# cubey_v3_1.net
KiCad netlist of a schematic drawn in EAGLE
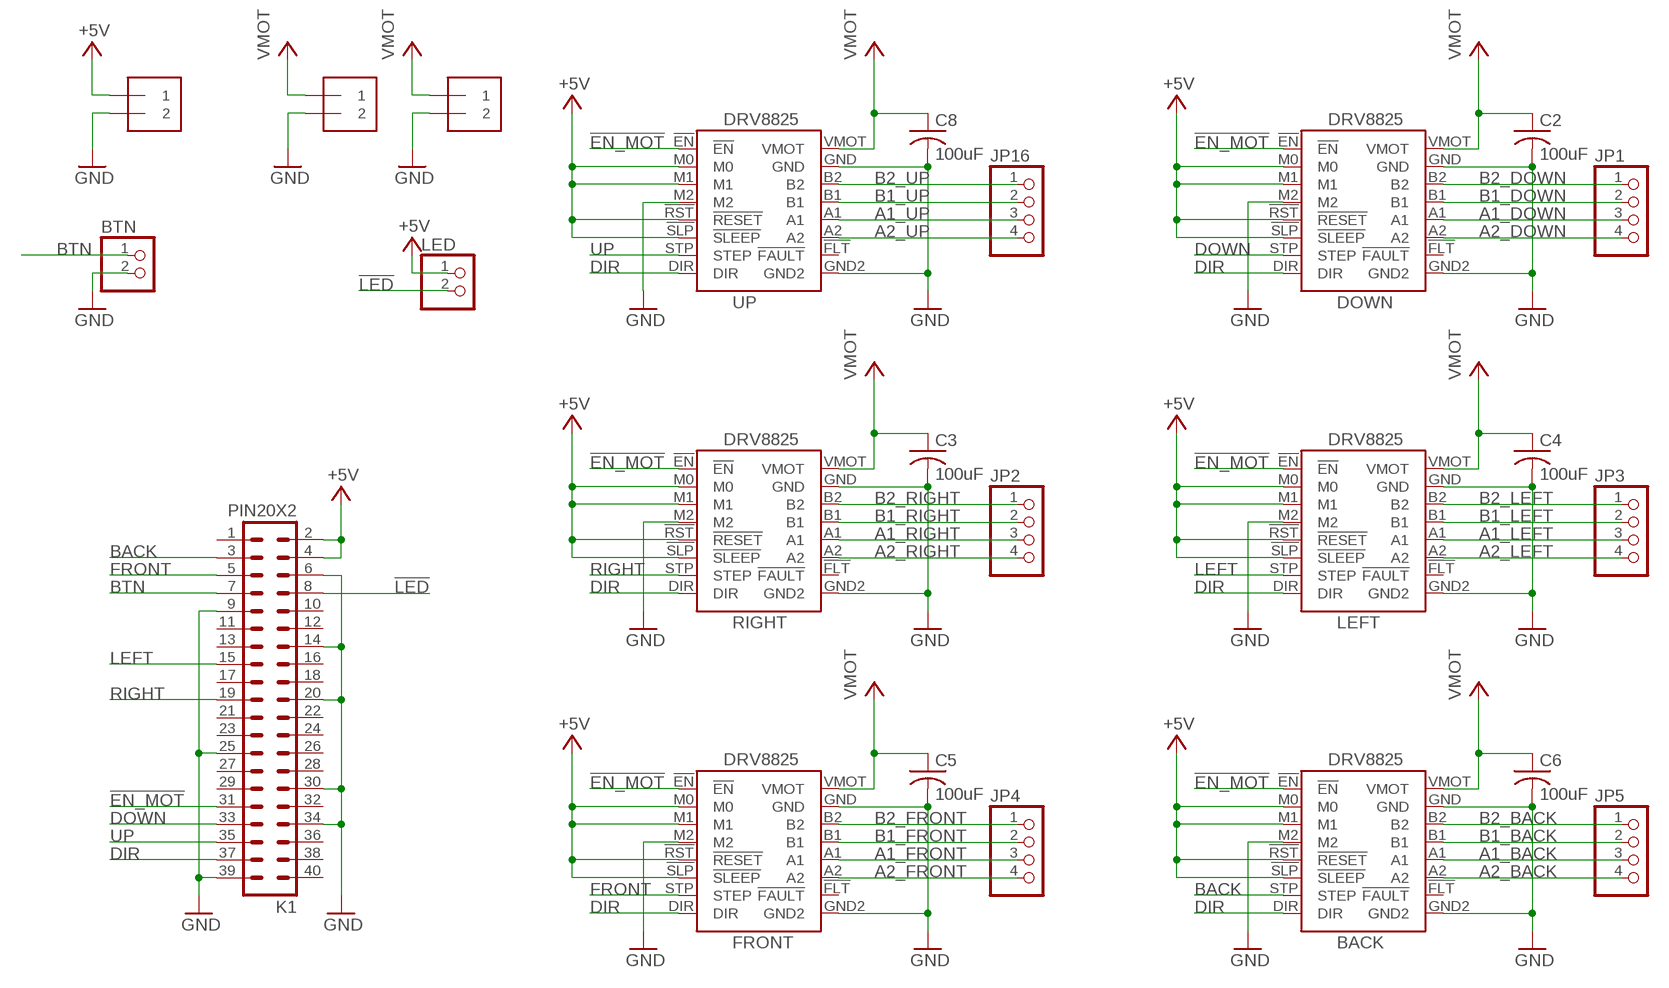
[diagram p0: schematic, sheet 1]

(export (version "E")
  (design (tool "Eeschema 10.0.6"))
  (components
    (comp (ref "5V_PWR")
      (value "1X2-3.5MM")
      (footprint "eagle-import:1X2-3.5MM")
      (libsource (lib "eagle-import") (part "1X2-3.5MM"))
    )
    (comp (ref "BACK")
      (value "DRV_8825_SOCKET")
      (footprint "eagle-import:DRV_8825_DIP")
      (libsource (lib "eagle-import") (part "DRV_8825_SOCKET"))
    )
    (comp (ref "BTN")
      (value "PINHD-1X2")
      (footprint "eagle-import:1X02")
      (libsource (lib "eagle-import") (part "PINHD-1X2"))
    )
    (comp (ref "C2")
      (value "100uF")
      (footprint "eagle-import:C025-025X050")
      (libsource (lib "eagle-import") (part "C-US025-025X050"))
    )
    (comp (ref "C3")
      (value "100uF")
      (footprint "eagle-import:C025-025X050")
      (libsource (lib "eagle-import") (part "C-US025-025X050"))
    )
    (comp (ref "C4")
      (value "100uF")
      (footprint "eagle-import:C025-025X050")
      (libsource (lib "eagle-import") (part "C-US025-025X050"))
    )
    (comp (ref "C5")
      (value "100uF")
      (footprint "eagle-import:C025-025X050")
      (libsource (lib "eagle-import") (part "C-US025-025X050"))
    )
    (comp (ref "C6")
      (value "100uF")
      (footprint "eagle-import:C025-025X050")
      (libsource (lib "eagle-import") (part "C-US025-025X050"))
    )
    (comp (ref "C8")
      (value "100uF")
      (footprint "eagle-import:C025-025X050")
      (libsource (lib "eagle-import") (part "C-US025-025X050"))
    )
    (comp (ref "DOWN")
      (value "DRV_8825_SOCKET")
      (footprint "eagle-import:DRV_8825_DIP")
      (libsource (lib "eagle-import") (part "DRV_8825_SOCKET"))
    )
    (comp (ref "FRONT")
      (value "DRV_8825_SOCKET")
      (footprint "eagle-import:DRV_8825_DIP")
      (libsource (lib "eagle-import") (part "DRV_8825_SOCKET"))
    )
    (comp (ref "JP1")
      (value "PINHD-1X4")
      (footprint "eagle-import:1X04")
      (libsource (lib "eagle-import") (part "PINHD-1X4"))
    )
    (comp (ref "JP2")
      (value "PINHD-1X4")
      (footprint "eagle-import:1X04")
      (libsource (lib "eagle-import") (part "PINHD-1X4"))
    )
    (comp (ref "JP3")
      (value "PINHD-1X4")
      (footprint "eagle-import:1X04")
      (libsource (lib "eagle-import") (part "PINHD-1X4"))
    )
    (comp (ref "JP4")
      (value "PINHD-1X4")
      (footprint "eagle-import:1X04")
      (libsource (lib "eagle-import") (part "PINHD-1X4"))
    )
    (comp (ref "JP5")
      (value "PINHD-1X4")
      (footprint "eagle-import:1X04")
      (libsource (lib "eagle-import") (part "PINHD-1X4"))
    )
    (comp (ref "JP16")
      (value "PINHD-1X4")
      (footprint "eagle-import:1X04")
      (libsource (lib "eagle-import") (part "PINHD-1X4"))
    )
    (comp (ref "K1")
      (value "PIN20X2")
      (footprint "eagle-import:PIN_20X2")
      (libsource (lib "eagle-import") (part "PIN20X2"))
    )
    (comp (ref "LED")
      (value "PINHD-1X2")
      (footprint "eagle-import:1X02")
      (libsource (lib "eagle-import") (part "PINHD-1X2"))
    )
    (comp (ref "LEFT")
      (value "DRV_8825_SOCKET")
      (footprint "eagle-import:DRV_8825_DIP")
      (libsource (lib "eagle-import") (part "DRV_8825_SOCKET"))
    )
    (comp (ref "MOT_PWR")
      (value "1X2-3.5MM")
      (footprint "eagle-import:1X2-3.5MM")
      (libsource (lib "eagle-import") (part "1X2-3.5MM"))
    )
    (comp (ref "MOT_PWR1")
      (value "1X2-3.5MM")
      (footprint "eagle-import:1X2-3.5MM")
      (libsource (lib "eagle-import") (part "1X2-3.5MM"))
    )
    (comp (ref "RIGHT")
      (value "DRV_8825_SOCKET")
      (footprint "eagle-import:DRV_8825_DIP")
      (libsource (lib "eagle-import") (part "DRV_8825_SOCKET"))
    )
    (comp (ref "UP")
      (value "DRV_8825_SOCKET")
      (footprint "eagle-import:DRV_8825_DIP")
      (libsource (lib "eagle-import") (part "DRV_8825_SOCKET"))
    )
  )
  (nets
    (net (code "1") (name "+5V") (class "Default")
      (node (ref "5V_PWR") (pin "1") (pinfunction "1_1") (pintype "passive"))
      (node (ref "BACK") (pin "!RST") (pinfunction "~{RESET}_!RST") (pintype "bidirectional"))
      (node (ref "BACK") (pin "!SLP") (pinfunction "~{SLEEP}_!SLP") (pintype "bidirectional"))
      (node (ref "BACK") (pin "M0") (pinfunction "M0_M0") (pintype "bidirectional"))
      (node (ref "BACK") (pin "M1") (pinfunction "M1_M1") (pintype "bidirectional"))
      (node (ref "DOWN") (pin "!RST") (pinfunction "~{RESET}_!RST") (pintype "bidirectional"))
      (node (ref "DOWN") (pin "!SLP") (pinfunction "~{SLEEP}_!SLP") (pintype "bidirectional"))
      (node (ref "DOWN") (pin "M0") (pinfunction "M0_M0") (pintype "bidirectional"))
      (node (ref "DOWN") (pin "M1") (pinfunction "M1_M1") (pintype "bidirectional"))
      (node (ref "FRONT") (pin "!RST") (pinfunction "~{RESET}_!RST") (pintype "bidirectional"))
      (node (ref "FRONT") (pin "!SLP") (pinfunction "~{SLEEP}_!SLP") (pintype "bidirectional"))
      (node (ref "FRONT") (pin "M0") (pinfunction "M0_M0") (pintype "bidirectional"))
      (node (ref "FRONT") (pin "M1") (pinfunction "M1_M1") (pintype "bidirectional"))
      (node (ref "K1") (pin "2") (pinfunction "2_2") (pintype "passive"))
      (node (ref "K1") (pin "4") (pinfunction "4_4") (pintype "passive"))
      (node (ref "LED") (pin "1") (pinfunction "1_1") (pintype "passive"))
      (node (ref "LEFT") (pin "!RST") (pinfunction "~{RESET}_!RST") (pintype "bidirectional"))
      (node (ref "LEFT") (pin "!SLP") (pinfunction "~{SLEEP}_!SLP") (pintype "bidirectional"))
      (node (ref "LEFT") (pin "M0") (pinfunction "M0_M0") (pintype "bidirectional"))
      (node (ref "LEFT") (pin "M1") (pinfunction "M1_M1") (pintype "bidirectional"))
      (node (ref "RIGHT") (pin "!RST") (pinfunction "~{RESET}_!RST") (pintype "bidirectional"))
      (node (ref "RIGHT") (pin "!SLP") (pinfunction "~{SLEEP}_!SLP") (pintype "bidirectional"))
      (node (ref "RIGHT") (pin "M0") (pinfunction "M0_M0") (pintype "bidirectional"))
      (node (ref "RIGHT") (pin "M1") (pinfunction "M1_M1") (pintype "bidirectional"))
      (node (ref "UP") (pin "!RST") (pinfunction "~{RESET}_!RST") (pintype "bidirectional"))
      (node (ref "UP") (pin "!SLP") (pinfunction "~{SLEEP}_!SLP") (pintype "bidirectional"))
      (node (ref "UP") (pin "M0") (pinfunction "M0_M0") (pintype "bidirectional"))
      (node (ref "UP") (pin "M1") (pinfunction "M1_M1") (pintype "bidirectional"))
    )
    (net (code "2") (name "/A1_BACK") (class "Default")
      (node (ref "BACK") (pin "A1") (pinfunction "A1_A1") (pintype "power_in"))
      (node (ref "JP5") (pin "3") (pinfunction "3_3") (pintype "passive"))
    )
    (net (code "3") (name "/A1_DOWN") (class "Default")
      (node (ref "DOWN") (pin "A1") (pinfunction "A1_A1") (pintype "power_in"))
      (node (ref "JP1") (pin "3") (pinfunction "3_3") (pintype "passive"))
    )
    (net (code "4") (name "/A1_FRONT") (class "Default")
      (node (ref "FRONT") (pin "A1") (pinfunction "A1_A1") (pintype "power_in"))
      (node (ref "JP4") (pin "3") (pinfunction "3_3") (pintype "passive"))
    )
    (net (code "5") (name "/A1_LEFT") (class "Default")
      (node (ref "JP3") (pin "3") (pinfunction "3_3") (pintype "passive"))
      (node (ref "LEFT") (pin "A1") (pinfunction "A1_A1") (pintype "power_in"))
    )
    (net (code "6") (name "/A1_RIGHT") (class "Default")
      (node (ref "JP2") (pin "3") (pinfunction "3_3") (pintype "passive"))
      (node (ref "RIGHT") (pin "A1") (pinfunction "A1_A1") (pintype "power_in"))
    )
    (net (code "7") (name "/A1_UP") (class "Default")
      (node (ref "JP16") (pin "3") (pinfunction "3_3") (pintype "passive"))
      (node (ref "UP") (pin "A1") (pinfunction "A1_A1") (pintype "power_in"))
    )
    (net (code "8") (name "/A2_BACK") (class "Default")
      (node (ref "BACK") (pin "A2") (pinfunction "A2_A2") (pintype "power_in"))
      (node (ref "JP5") (pin "4") (pinfunction "4_4") (pintype "passive"))
    )
    (net (code "9") (name "/A2_DOWN") (class "Default")
      (node (ref "DOWN") (pin "A2") (pinfunction "A2_A2") (pintype "power_in"))
      (node (ref "JP1") (pin "4") (pinfunction "4_4") (pintype "passive"))
    )
    (net (code "10") (name "/A2_FRONT") (class "Default")
      (node (ref "FRONT") (pin "A2") (pinfunction "A2_A2") (pintype "power_in"))
      (node (ref "JP4") (pin "4") (pinfunction "4_4") (pintype "passive"))
    )
    (net (code "11") (name "/A2_LEFT") (class "Default")
      (node (ref "JP3") (pin "4") (pinfunction "4_4") (pintype "passive"))
      (node (ref "LEFT") (pin "A2") (pinfunction "A2_A2") (pintype "power_in"))
    )
    (net (code "12") (name "/A2_RIGHT") (class "Default")
      (node (ref "JP2") (pin "4") (pinfunction "4_4") (pintype "passive"))
      (node (ref "RIGHT") (pin "A2") (pinfunction "A2_A2") (pintype "power_in"))
    )
    (net (code "13") (name "/A2_UP") (class "Default")
      (node (ref "JP16") (pin "4") (pinfunction "4_4") (pintype "passive"))
      (node (ref "UP") (pin "A2") (pinfunction "A2_A2") (pintype "power_in"))
    )
    (net (code "14") (name "/B1_BACK") (class "Default")
      (node (ref "BACK") (pin "B1") (pinfunction "B1_B1") (pintype "power_in"))
      (node (ref "JP5") (pin "2") (pinfunction "2_2") (pintype "passive"))
    )
    (net (code "15") (name "/B1_DOWN") (class "Default")
      (node (ref "DOWN") (pin "B1") (pinfunction "B1_B1") (pintype "power_in"))
      (node (ref "JP1") (pin "2") (pinfunction "2_2") (pintype "passive"))
    )
    (net (code "16") (name "/B1_FRONT") (class "Default")
      (node (ref "FRONT") (pin "B1") (pinfunction "B1_B1") (pintype "power_in"))
      (node (ref "JP4") (pin "2") (pinfunction "2_2") (pintype "passive"))
    )
    (net (code "17") (name "/B1_LEFT") (class "Default")
      (node (ref "JP3") (pin "2") (pinfunction "2_2") (pintype "passive"))
      (node (ref "LEFT") (pin "B1") (pinfunction "B1_B1") (pintype "power_in"))
    )
    (net (code "18") (name "/B1_RIGHT") (class "Default")
      (node (ref "JP2") (pin "2") (pinfunction "2_2") (pintype "passive"))
      (node (ref "RIGHT") (pin "B1") (pinfunction "B1_B1") (pintype "power_in"))
    )
    (net (code "19") (name "/B1_UP") (class "Default")
      (node (ref "JP16") (pin "2") (pinfunction "2_2") (pintype "passive"))
      (node (ref "UP") (pin "B1") (pinfunction "B1_B1") (pintype "power_in"))
    )
    (net (code "20") (name "/B2_BACK") (class "Default")
      (node (ref "BACK") (pin "B2") (pinfunction "B2_B2") (pintype "power_in"))
      (node (ref "JP5") (pin "1") (pinfunction "1_1") (pintype "passive"))
    )
    (net (code "21") (name "/B2_DOWN") (class "Default")
      (node (ref "DOWN") (pin "B2") (pinfunction "B2_B2") (pintype "power_in"))
      (node (ref "JP1") (pin "1") (pinfunction "1_1") (pintype "passive"))
    )
    (net (code "22") (name "/B2_FRONT") (class "Default")
      (node (ref "FRONT") (pin "B2") (pinfunction "B2_B2") (pintype "power_in"))
      (node (ref "JP4") (pin "1") (pinfunction "1_1") (pintype "passive"))
    )
    (net (code "23") (name "/B2_LEFT") (class "Default")
      (node (ref "JP3") (pin "1") (pinfunction "1_1") (pintype "passive"))
      (node (ref "LEFT") (pin "B2") (pinfunction "B2_B2") (pintype "power_in"))
    )
    (net (code "24") (name "/B2_RIGHT") (class "Default")
      (node (ref "JP2") (pin "1") (pinfunction "1_1") (pintype "passive"))
      (node (ref "RIGHT") (pin "B2") (pinfunction "B2_B2") (pintype "power_in"))
    )
    (net (code "25") (name "/B2_UP") (class "Default")
      (node (ref "JP16") (pin "1") (pinfunction "1_1") (pintype "passive"))
      (node (ref "UP") (pin "B2") (pinfunction "B2_B2") (pintype "power_in"))
    )
    (net (code "26") (name "/BACK") (class "Default")
      (node (ref "BACK") (pin "STP") (pinfunction "STEP_STP") (pintype "bidirectional"))
      (node (ref "K1") (pin "3") (pinfunction "3_3") (pintype "passive"))
    )
    (net (code "27") (name "/BTN") (class "Default")
      (node (ref "BTN") (pin "1") (pinfunction "1_1") (pintype "passive"))
      (node (ref "K1") (pin "7") (pinfunction "7_7") (pintype "passive"))
    )
    (net (code "28") (name "/DIR") (class "Default")
      (node (ref "BACK") (pin "DIR") (pinfunction "DIR_DIR") (pintype "bidirectional"))
      (node (ref "DOWN") (pin "DIR") (pinfunction "DIR_DIR") (pintype "bidirectional"))
      (node (ref "FRONT") (pin "DIR") (pinfunction "DIR_DIR") (pintype "bidirectional"))
      (node (ref "K1") (pin "37") (pinfunction "37_37") (pintype "passive"))
      (node (ref "LEFT") (pin "DIR") (pinfunction "DIR_DIR") (pintype "bidirectional"))
      (node (ref "RIGHT") (pin "DIR") (pinfunction "DIR_DIR") (pintype "bidirectional"))
      (node (ref "UP") (pin "DIR") (pinfunction "DIR_DIR") (pintype "bidirectional"))
    )
    (net (code "29") (name "/DOWN") (class "Default")
      (node (ref "DOWN") (pin "STP") (pinfunction "STEP_STP") (pintype "bidirectional"))
      (node (ref "K1") (pin "33") (pinfunction "33_33") (pintype "passive"))
    )
    (net (code "30") (name "/FRONT") (class "Default")
      (node (ref "FRONT") (pin "STP") (pinfunction "STEP_STP") (pintype "bidirectional"))
      (node (ref "K1") (pin "5") (pinfunction "5_5") (pintype "passive"))
    )
    (net (code "31") (name "/LEFT") (class "Default")
      (node (ref "K1") (pin "15") (pinfunction "15_15") (pintype "passive"))
      (node (ref "LEFT") (pin "STP") (pinfunction "STEP_STP") (pintype "bidirectional"))
    )
    (net (code "32") (name "/RIGHT") (class "Default")
      (node (ref "K1") (pin "19") (pinfunction "19_19") (pintype "passive"))
      (node (ref "RIGHT") (pin "STP") (pinfunction "STEP_STP") (pintype "bidirectional"))
    )
    (net (code "33") (name "/UP") (class "Default")
      (node (ref "K1") (pin "35") (pinfunction "35_35") (pintype "passive"))
      (node (ref "UP") (pin "STP") (pinfunction "STEP_STP") (pintype "bidirectional"))
    )
    (net (code "34") (name "/~{EN_MOT}") (class "Default")
      (node (ref "BACK") (pin "!EN") (pinfunction "~{EN}_!EN") (pintype "bidirectional"))
      (node (ref "DOWN") (pin "!EN") (pinfunction "~{EN}_!EN") (pintype "bidirectional"))
      (node (ref "FRONT") (pin "!EN") (pinfunction "~{EN}_!EN") (pintype "bidirectional"))
      (node (ref "K1") (pin "31") (pinfunction "31_31") (pintype "passive"))
      (node (ref "LEFT") (pin "!EN") (pinfunction "~{EN}_!EN") (pintype "bidirectional"))
      (node (ref "RIGHT") (pin "!EN") (pinfunction "~{EN}_!EN") (pintype "bidirectional"))
      (node (ref "UP") (pin "!EN") (pinfunction "~{EN}_!EN") (pintype "bidirectional"))
    )
    (net (code "35") (name "/~{LED}") (class "Default")
      (node (ref "K1") (pin "8") (pinfunction "8_8") (pintype "passive"))
      (node (ref "LED") (pin "2") (pinfunction "2_2") (pintype "passive"))
    )
    (net (code "36") (name "GND") (class "Default")
      (node (ref "5V_PWR") (pin "2") (pinfunction "2_2") (pintype "passive"))
      (node (ref "BACK") (pin "GND") (pinfunction "GND_GND") (pintype "power_in"))
      (node (ref "BACK") (pin "GND2") (pinfunction "GND2_GND2") (pintype "power_in"))
      (node (ref "BACK") (pin "M2") (pinfunction "M2_M2") (pintype "bidirectional"))
      (node (ref "BTN") (pin "2") (pinfunction "2_2") (pintype "passive"))
      (node (ref "C2") (pin "2") (pinfunction "2_2") (pintype "passive"))
      (node (ref "C3") (pin "2") (pinfunction "2_2") (pintype "passive"))
      (node (ref "C4") (pin "2") (pinfunction "2_2") (pintype "passive"))
      (node (ref "C5") (pin "2") (pinfunction "2_2") (pintype "passive"))
      (node (ref "C6") (pin "2") (pinfunction "2_2") (pintype "passive"))
      (node (ref "C8") (pin "2") (pinfunction "2_2") (pintype "passive"))
      (node (ref "DOWN") (pin "GND") (pinfunction "GND_GND") (pintype "power_in"))
      (node (ref "DOWN") (pin "GND2") (pinfunction "GND2_GND2") (pintype "power_in"))
      (node (ref "DOWN") (pin "M2") (pinfunction "M2_M2") (pintype "bidirectional"))
      (node (ref "FRONT") (pin "GND") (pinfunction "GND_GND") (pintype "power_in"))
      (node (ref "FRONT") (pin "GND2") (pinfunction "GND2_GND2") (pintype "power_in"))
      (node (ref "FRONT") (pin "M2") (pinfunction "M2_M2") (pintype "bidirectional"))
      (node (ref "K1") (pin "14") (pinfunction "14_14") (pintype "passive"))
      (node (ref "K1") (pin "20") (pinfunction "20_20") (pintype "passive"))
      (node (ref "K1") (pin "25") (pinfunction "25_25") (pintype "passive"))
      (node (ref "K1") (pin "30") (pinfunction "30_30") (pintype "passive"))
      (node (ref "K1") (pin "34") (pinfunction "34_34") (pintype "passive"))
      (node (ref "K1") (pin "39") (pinfunction "39_39") (pintype "passive"))
      (node (ref "K1") (pin "6") (pinfunction "6_6") (pintype "passive"))
      (node (ref "K1") (pin "9") (pinfunction "9_9") (pintype "passive"))
      (node (ref "LEFT") (pin "GND") (pinfunction "GND_GND") (pintype "power_in"))
      (node (ref "LEFT") (pin "GND2") (pinfunction "GND2_GND2") (pintype "power_in"))
      (node (ref "LEFT") (pin "M2") (pinfunction "M2_M2") (pintype "bidirectional"))
      (node (ref "MOT_PWR") (pin "2") (pinfunction "2_2") (pintype "passive"))
      (node (ref "MOT_PWR1") (pin "2") (pinfunction "2_2") (pintype "passive"))
      (node (ref "RIGHT") (pin "GND") (pinfunction "GND_GND") (pintype "power_in"))
      (node (ref "RIGHT") (pin "GND2") (pinfunction "GND2_GND2") (pintype "power_in"))
      (node (ref "RIGHT") (pin "M2") (pinfunction "M2_M2") (pintype "bidirectional"))
      (node (ref "UP") (pin "GND") (pinfunction "GND_GND") (pintype "power_in"))
      (node (ref "UP") (pin "GND2") (pinfunction "GND2_GND2") (pintype "power_in"))
      (node (ref "UP") (pin "M2") (pinfunction "M2_M2") (pintype "bidirectional"))
    )
    (net (code "37") (name "VMOT") (class "Default")
      (node (ref "BACK") (pin "VMOT") (pinfunction "VMOT_VMOT") (pintype "power_in"))
      (node (ref "C2") (pin "1") (pinfunction "1_1") (pintype "passive"))
      (node (ref "C3") (pin "1") (pinfunction "1_1") (pintype "passive"))
      (node (ref "C4") (pin "1") (pinfunction "1_1") (pintype "passive"))
      (node (ref "C5") (pin "1") (pinfunction "1_1") (pintype "passive"))
      (node (ref "C6") (pin "1") (pinfunction "1_1") (pintype "passive"))
      (node (ref "C8") (pin "1") (pinfunction "1_1") (pintype "passive"))
      (node (ref "DOWN") (pin "VMOT") (pinfunction "VMOT_VMOT") (pintype "power_in"))
      (node (ref "FRONT") (pin "VMOT") (pinfunction "VMOT_VMOT") (pintype "power_in"))
      (node (ref "LEFT") (pin "VMOT") (pinfunction "VMOT_VMOT") (pintype "power_in"))
      (node (ref "MOT_PWR") (pin "1") (pinfunction "1_1") (pintype "passive"))
      (node (ref "MOT_PWR1") (pin "1") (pinfunction "1_1") (pintype "passive"))
      (node (ref "RIGHT") (pin "VMOT") (pinfunction "VMOT_VMOT") (pintype "power_in"))
      (node (ref "UP") (pin "VMOT") (pinfunction "VMOT_VMOT") (pintype "power_in"))
    )
    (net (code "38") (name "unconnected-(BACK-~{FAULT}-Pad!FLT)") (class "Default")
      (node (ref "BACK") (pin "!FLT") (pinfunction "~{FAULT}_!FLT") (pintype "bidirectional"))
    )
    (net (code "39") (name "unconnected-(DOWN-~{FAULT}-Pad!FLT)") (class "Default")
      (node (ref "DOWN") (pin "!FLT") (pinfunction "~{FAULT}_!FLT") (pintype "bidirectional"))
    )
    (net (code "40") (name "unconnected-(FRONT-~{FAULT}-Pad!FLT)") (class "Default")
      (node (ref "FRONT") (pin "!FLT") (pinfunction "~{FAULT}_!FLT") (pintype "bidirectional"))
    )
    (net (code "41") (name "unconnected-(K1-Pad1)") (class "Default")
      (node (ref "K1") (pin "1") (pinfunction "1_1") (pintype "passive"))
    )
    (net (code "42") (name "unconnected-(K1-Pad10)") (class "Default")
      (node (ref "K1") (pin "10") (pinfunction "10_10") (pintype "passive"))
    )
    (net (code "43") (name "unconnected-(K1-Pad11)") (class "Default")
      (node (ref "K1") (pin "11") (pinfunction "11_11") (pintype "passive"))
    )
    (net (code "44") (name "unconnected-(K1-Pad12)") (class "Default")
      (node (ref "K1") (pin "12") (pinfunction "12_12") (pintype "passive"))
    )
    (net (code "45") (name "unconnected-(K1-Pad13)") (class "Default")
      (node (ref "K1") (pin "13") (pinfunction "13_13") (pintype "passive"))
    )
    (net (code "46") (name "unconnected-(K1-Pad16)") (class "Default")
      (node (ref "K1") (pin "16") (pinfunction "16_16") (pintype "passive"))
    )
    (net (code "47") (name "unconnected-(K1-Pad17)") (class "Default")
      (node (ref "K1") (pin "17") (pinfunction "17_17") (pintype "passive"))
    )
    (net (code "48") (name "unconnected-(K1-Pad18)") (class "Default")
      (node (ref "K1") (pin "18") (pinfunction "18_18") (pintype "passive"))
    )
    (net (code "49") (name "unconnected-(K1-Pad21)") (class "Default")
      (node (ref "K1") (pin "21") (pinfunction "21_21") (pintype "passive"))
    )
    (net (code "50") (name "unconnected-(K1-Pad22)") (class "Default")
      (node (ref "K1") (pin "22") (pinfunction "22_22") (pintype "passive"))
    )
    (net (code "51") (name "unconnected-(K1-Pad23)") (class "Default")
      (node (ref "K1") (pin "23") (pinfunction "23_23") (pintype "passive"))
    )
    (net (code "52") (name "unconnected-(K1-Pad24)") (class "Default")
      (node (ref "K1") (pin "24") (pinfunction "24_24") (pintype "passive"))
    )
    (net (code "53") (name "unconnected-(K1-Pad26)") (class "Default")
      (node (ref "K1") (pin "26") (pinfunction "26_26") (pintype "passive"))
    )
    (net (code "54") (name "unconnected-(K1-Pad27)") (class "Default")
      (node (ref "K1") (pin "27") (pinfunction "27_27") (pintype "passive"))
    )
    (net (code "55") (name "unconnected-(K1-Pad28)") (class "Default")
      (node (ref "K1") (pin "28") (pinfunction "28_28") (pintype "passive"))
    )
    (net (code "56") (name "unconnected-(K1-Pad29)") (class "Default")
      (node (ref "K1") (pin "29") (pinfunction "29_29") (pintype "passive"))
    )
    (net (code "57") (name "unconnected-(K1-Pad32)") (class "Default")
      (node (ref "K1") (pin "32") (pinfunction "32_32") (pintype "passive"))
    )
    (net (code "58") (name "unconnected-(K1-Pad36)") (class "Default")
      (node (ref "K1") (pin "36") (pinfunction "36_36") (pintype "passive"))
    )
    (net (code "59") (name "unconnected-(K1-Pad38)") (class "Default")
      (node (ref "K1") (pin "38") (pinfunction "38_38") (pintype "passive"))
    )
    (net (code "60") (name "unconnected-(K1-Pad40)") (class "Default")
      (node (ref "K1") (pin "40") (pinfunction "40_40") (pintype "passive"))
    )
    (net (code "61") (name "unconnected-(LEFT-~{FAULT}-Pad!FLT)") (class "Default")
      (node (ref "LEFT") (pin "!FLT") (pinfunction "~{FAULT}_!FLT") (pintype "bidirectional"))
    )
    (net (code "62") (name "unconnected-(RIGHT-~{FAULT}-Pad!FLT)") (class "Default")
      (node (ref "RIGHT") (pin "!FLT") (pinfunction "~{FAULT}_!FLT") (pintype "bidirectional"))
    )
    (net (code "63") (name "unconnected-(UP-~{FAULT}-Pad!FLT)") (class "Default")
      (node (ref "UP") (pin "!FLT") (pinfunction "~{FAULT}_!FLT") (pintype "bidirectional"))
    )
  )
)
